# Attiny_pjon_sensor_corriente_ICSP.net
KiCad netlist of a schematic drawn in EAGLE
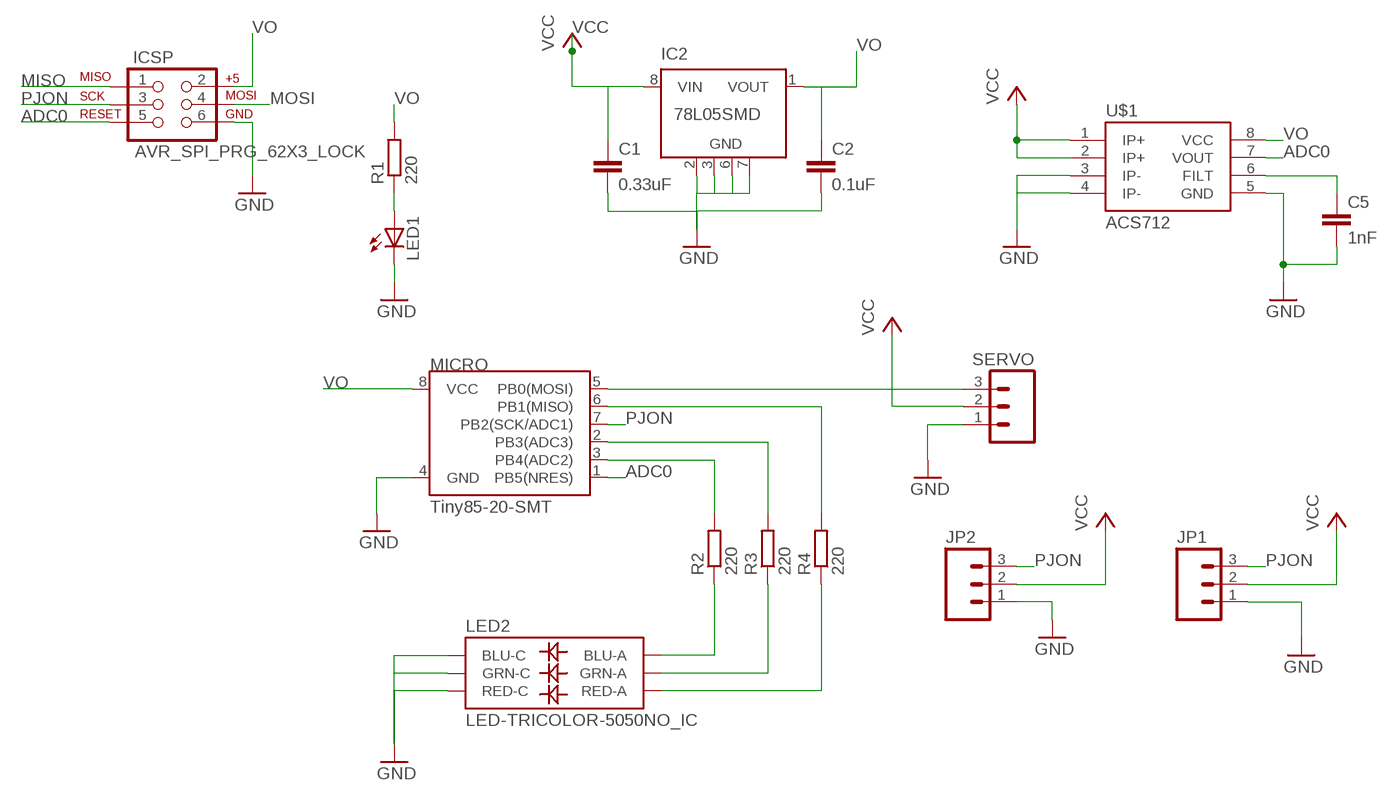
[diagram p0: schematic, sheet 1]

(export (version "E")
  (design (tool "Eeschema 10.0.6"))
  (components
    (comp (ref "C1")
      (value "0.33uF")
      (footprint "eagle-import:C1206")
      (libsource (lib "eagle-import") (part "C-EUC1206"))
    )
    (comp (ref "C2")
      (value "0.1uF")
      (footprint "eagle-import:C1206")
      (libsource (lib "eagle-import") (part "C-EUC1206"))
    )
    (comp (ref "C5")
      (value "1nF")
      (footprint "eagle-import:C1206")
      (libsource (lib "eagle-import") (part "C-EUC1206"))
    )
    (comp (ref "IC2")
      (value "78L05SMD")
      (footprint "eagle-import:SO08")
      (libsource (lib "eagle-import") (part "78LSMD05"))
    )
    (comp (ref "ICSP")
      (value "AVR_SPI_PRG_62X3_LOCK")
      (footprint "eagle-import:2X3_LOCK")
      (libsource (lib "eagle-import") (part "AVR_SPI_PRG_62X3_LOCK"))
    )
    (comp (ref "JP1")
      (value "M03PTH")
      (footprint "eagle-import:1X03")
      (libsource (lib "eagle-import") (part "M03PTH"))
    )
    (comp (ref "JP2")
      (value "M03PTH")
      (footprint "eagle-import:1X03")
      (libsource (lib "eagle-import") (part "M03PTH"))
    )
    (comp (ref "LED1")
      (value "LEDSMT1206")
      (footprint "eagle-import:1206")
      (libsource (lib "eagle-import") (part "LEDSMT1206"))
    )
    (comp (ref "LED2")
      (value "LED-TRICOLOR-5050NO_IC")
      (footprint "eagle-import:LED-TRICOLOR-5050")
      (libsource (lib "eagle-import") (part "LED-TRICOLOR-5050NO_IC"))
    )
    (comp (ref "MICRO")
      (value "Tiny85-20-SMT")
      (footprint "eagle-import:SO08-EIAJ")
      (libsource (lib "eagle-import") (part "ATTINY45TINY85-20-SMT"))
    )
    (comp (ref "R1")
      (value "220")
      (footprint "eagle-import:R1206")
      (libsource (lib "eagle-import") (part "R-EU_R1206"))
    )
    (comp (ref "R2")
      (value "220")
      (footprint "eagle-import:R1206")
      (libsource (lib "eagle-import") (part "R-EU_R1206"))
    )
    (comp (ref "R3")
      (value "220")
      (footprint "eagle-import:R1206")
      (libsource (lib "eagle-import") (part "R-EU_R1206"))
    )
    (comp (ref "R4")
      (value "220")
      (footprint "eagle-import:R1206")
      (libsource (lib "eagle-import") (part "R-EU_R1206"))
    )
    (comp (ref "SERVO")
      (value "M03PTH")
      (footprint "eagle-import:1X03")
      (libsource (lib "eagle-import") (part "M03PTH"))
    )
    (comp (ref "U$1")
      (value "ACS712")
      (footprint "eagle-import:SO08")
      (libsource (lib "eagle-import") (part "ACS712"))
    )
  )
  (nets
    (net (code "1") (name "/ADC0") (class "Default")
      (node (ref "ICSP") (pin "5") (pinfunction "5_5") (pintype "passive"))
      (node (ref "MICRO") (pin "1") (pinfunction "PB5(NRES)_1") (pintype "bidirectional"))
      (node (ref "U$1") (pin "7") (pinfunction "VOUT_7") (pintype "bidirectional"))
    )
    (net (code "2") (name "/MISO") (class "Default")
      (node (ref "ICSP") (pin "1") (pinfunction "1_1") (pintype "passive"))
      (node (ref "MICRO") (pin "6") (pinfunction "PB1(MISO)_6") (pintype "bidirectional"))
      (node (ref "R4") (pin "2") (pinfunction "2_2") (pintype "passive"))
    )
    (net (code "3") (name "/MOSI") (class "Default")
      (node (ref "ICSP") (pin "4") (pinfunction "4_4") (pintype "passive"))
      (node (ref "MICRO") (pin "5") (pinfunction "PB0(MOSI)_5") (pintype "bidirectional"))
      (node (ref "SERVO") (pin "3") (pinfunction "3_3") (pintype "passive"))
    )
    (net (code "4") (name "/PJON") (class "Default")
      (node (ref "ICSP") (pin "3") (pinfunction "3_3") (pintype "passive"))
      (node (ref "JP1") (pin "3") (pinfunction "3_3") (pintype "passive"))
      (node (ref "JP2") (pin "3") (pinfunction "3_3") (pintype "passive"))
      (node (ref "MICRO") (pin "7") (pinfunction "PB2(SCK/ADC1)_7") (pintype "bidirectional"))
    )
    (net (code "5") (name "/VO") (class "Default")
      (node (ref "C2") (pin "1") (pinfunction "1_1") (pintype "passive"))
      (node (ref "IC2") (pin "1") (pinfunction "VOUT_1") (pintype "output"))
      (node (ref "ICSP") (pin "2") (pinfunction "2_2") (pintype "passive"))
      (node (ref "MICRO") (pin "8") (pinfunction "VCC_8") (pintype "bidirectional"))
      (node (ref "R1") (pin "2") (pinfunction "2_2") (pintype "passive"))
      (node (ref "U$1") (pin "8") (pinfunction "VCC_8") (pintype "bidirectional"))
    )
    (net (code "6") (name "GND") (class "Default")
      (node (ref "C1") (pin "2") (pinfunction "2_2") (pintype "passive"))
      (node (ref "C2") (pin "2") (pinfunction "2_2") (pintype "passive"))
      (node (ref "C5") (pin "2") (pinfunction "2_2") (pintype "passive"))
      (node (ref "IC2") (pin "2") (pinfunction "GND_2") (pintype "power_in"))
      (node (ref "IC2") (pin "3") (pinfunction "GND_3") (pintype "power_in"))
      (node (ref "IC2") (pin "6") (pinfunction "GND_6") (pintype "power_in"))
      (node (ref "IC2") (pin "7") (pinfunction "GND_7") (pintype "power_in"))
      (node (ref "ICSP") (pin "6") (pinfunction "6_6") (pintype "passive"))
      (node (ref "JP1") (pin "1") (pinfunction "1_1") (pintype "passive"))
      (node (ref "JP2") (pin "1") (pinfunction "1_1") (pintype "passive"))
      (node (ref "LED1") (pin "C") (pinfunction "C_C") (pintype "passive"))
      (node (ref "LED2") (pin "4") (pinfunction "BLU-C_4") (pintype "bidirectional"))
      (node (ref "LED2") (pin "5") (pinfunction "RED-C_5") (pintype "bidirectional"))
      (node (ref "LED2") (pin "6") (pinfunction "GRN-C_6") (pintype "bidirectional"))
      (node (ref "MICRO") (pin "4") (pinfunction "GND_4") (pintype "bidirectional"))
      (node (ref "SERVO") (pin "1") (pinfunction "1_1") (pintype "passive"))
      (node (ref "U$1") (pin "3") (pinfunction "IP-_3") (pintype "bidirectional"))
      (node (ref "U$1") (pin "4") (pinfunction "IP-_4") (pintype "bidirectional"))
      (node (ref "U$1") (pin "5") (pinfunction "GND_5") (pintype "bidirectional"))
    )
    (net (code "7") (name "Net-(LED1-PadA)") (class "Default")
      (node (ref "LED1") (pin "A") (pinfunction "A_A") (pintype "passive"))
      (node (ref "R1") (pin "1") (pinfunction "1_1") (pintype "passive"))
    )
    (net (code "8") (name "Net-(LED2-BLU-A)") (class "Default")
      (node (ref "LED2") (pin "3") (pinfunction "BLU-A_3") (pintype "bidirectional"))
      (node (ref "R2") (pin "1") (pinfunction "1_1") (pintype "passive"))
    )
    (net (code "9") (name "Net-(LED2-GRN-A)") (class "Default")
      (node (ref "LED2") (pin "1") (pinfunction "GRN-A_1") (pintype "bidirectional"))
      (node (ref "R3") (pin "1") (pinfunction "1_1") (pintype "passive"))
    )
    (net (code "10") (name "Net-(LED2-RED-A)") (class "Default")
      (node (ref "LED2") (pin "2") (pinfunction "RED-A_2") (pintype "bidirectional"))
      (node (ref "R4") (pin "1") (pinfunction "1_1") (pintype "passive"))
    )
    (net (code "11") (name "Net-(MICRO-PB3(ADC3))") (class "Default")
      (node (ref "MICRO") (pin "2") (pinfunction "PB3(ADC3)_2") (pintype "bidirectional"))
      (node (ref "R3") (pin "2") (pinfunction "2_2") (pintype "passive"))
    )
    (net (code "12") (name "Net-(MICRO-PB4(ADC2))") (class "Default")
      (node (ref "MICRO") (pin "3") (pinfunction "PB4(ADC2)_3") (pintype "bidirectional"))
      (node (ref "R2") (pin "2") (pinfunction "2_2") (pintype "passive"))
    )
    (net (code "13") (name "Net-(U$1-FILT)") (class "Default")
      (node (ref "C5") (pin "1") (pinfunction "1_1") (pintype "passive"))
      (node (ref "U$1") (pin "6") (pinfunction "FILT_6") (pintype "bidirectional"))
    )
    (net (code "14") (name "VCC") (class "Default")
      (node (ref "C1") (pin "1") (pinfunction "1_1") (pintype "passive"))
      (node (ref "IC2") (pin "8") (pinfunction "VIN_8") (pintype "passive"))
      (node (ref "JP1") (pin "2") (pinfunction "2_2") (pintype "passive"))
      (node (ref "JP2") (pin "2") (pinfunction "2_2") (pintype "passive"))
      (node (ref "SERVO") (pin "2") (pinfunction "2_2") (pintype "passive"))
      (node (ref "U$1") (pin "1") (pinfunction "IP+_1") (pintype "bidirectional"))
      (node (ref "U$1") (pin "2") (pinfunction "IP+_2") (pintype "bidirectional"))
    )
  )
)
